# Sheet1.net
KiCad netlist of a schematic drawn in Altium Designer
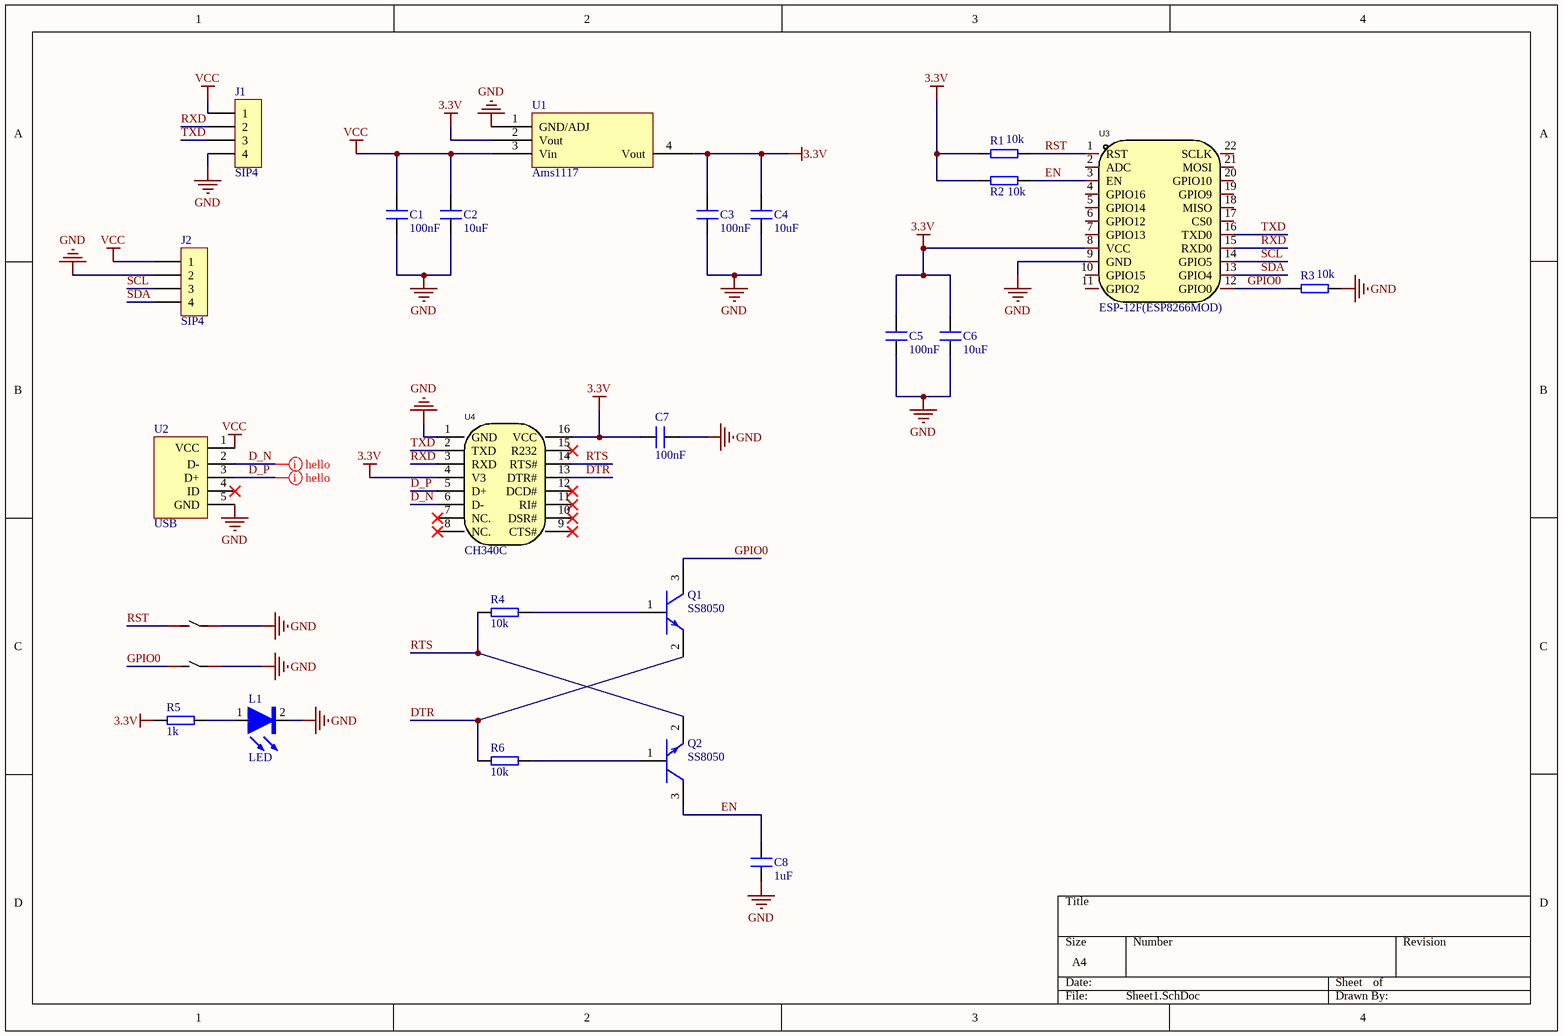
[diagram p0: Sheet1.SchDoc]

(export (version "E")
  (design (tool "Eeschema 10.0.6"))
  (components
    (comp (ref "C1")
      (value "100nF")
      (footprint "0805C")
      (description "电容")
      (libsource (lib "YTschlib") (part "CAP"))
    )
    (comp (ref "C2")
      (value "10uF")
      (footprint "0805C")
      (description "电容")
      (libsource (lib "YTschlib") (part "CAP"))
    )
    (comp (ref "C3")
      (value "100nF")
      (footprint "0805C")
      (description "电容")
      (libsource (lib "YTschlib") (part "CAP"))
    )
    (comp (ref "C4")
      (value "10uF")
      (footprint "0805C")
      (description "电容")
      (libsource (lib "YTschlib") (part "CAP"))
    )
    (comp (ref "C5")
      (value "100nF")
      (footprint "0805C")
      (description "电容")
      (libsource (lib "YTschlib") (part "CAP"))
    )
    (comp (ref "C6")
      (value "10uF")
      (footprint "0805C")
      (description "电容")
      (libsource (lib "YTschlib") (part "CAP"))
    )
    (comp (ref "C7")
      (value "100nF")
      (footprint "0805C")
      (description "电容")
      (libsource (lib "YTschlib") (part "CAP"))
    )
    (comp (ref "C8")
      (value "1uF")
      (footprint "0805C")
      (description "电容")
      (libsource (lib "YTschlib") (part "CAP"))
    )
    (comp (ref "J1")
      (value "SIP4")
      (footprint "XH2.54-WS-4P")
      (description "jointbar")
      (libsource (lib "YTschlib") (part "SIP4"))
    )
    (comp (ref "J2")
      (value "SIP4")
      (footprint "SIP_4P-P2.54-V-F")
      (description "jointbar")
      (libsource (lib "YTschlib") (part "SIP4"))
    )
    (comp (ref "L1") (value "LED") (footprint "LED0603-R-RD_GREEN") (libsource (lib "YTschlib") (part "LED")))
    (comp (ref "Q1")
      (value "SS8050")
      (footprint "SOT-23-3_L2.9-W1.3-P1.90-LS2.4-BR")
      (libsource (lib "YTschlib") (part "SS8050"))
    )
    (comp (ref "Q2")
      (value "SS8050")
      (footprint "SOT-23-3_L2.9-W1.3-P1.90-LS2.4-BR")
      (libsource (lib "YTschlib") (part "SS8050"))
    )
    (comp (ref "R1")
      (value "10k")
      (footprint "0805R")
      (description "电阻")
      (libsource (lib "YTschlib") (part "RES"))
    )
    (comp (ref "R2")
      (value "10k")
      (footprint "0805R")
      (description "电阻")
      (libsource (lib "YTschlib") (part "RES"))
    )
    (comp (ref "R3")
      (value "10k")
      (footprint "0805R")
      (description "电阻")
      (libsource (lib "YTschlib") (part "RES"))
    )
    (comp (ref "R4")
      (value "10k")
      (footprint "0805R")
      (description "电阻")
      (libsource (lib "YTschlib") (part "RES"))
    )
    (comp (ref "R5")
      (value "1k")
      (footprint "0805R")
      (description "电阻")
      (libsource (lib "YTschlib") (part "RES"))
    )
    (comp (ref "R6")
      (value "10k")
      (footprint "0805R")
      (description "电阻")
      (libsource (lib "YTschlib") (part "RES"))
    )
    (comp (ref "SW1")
      (value "TS342A2P 250gf-WZ 021_C2987973")
      (footprint "SW-SMD_L4.0-W2.9-LS5.0")
      (fields
        (field (name "MANUFACTURER") "SHOU HAN(首韩)")
        (field (name "MANUFACTURER PART") "TS342A2P 250gf-WZ 021")
      )
      (libsource (lib "YTschlib") (part "SW"))
    )
    (comp (ref "SW2")
      (value "TS342A2P 250gf-WZ 021_C2987973")
      (footprint "SW-SMD_L4.0-W2.9-LS5.0")
      (fields
        (field (name "MANUFACTURER") "SHOU HAN(首韩)")
        (field (name "MANUFACTURER PART") "TS342A2P 250gf-WZ 021")
      )
      (libsource (lib "YTschlib") (part "SW"))
    )
    (comp (ref "U1")
      (value "Ams1117")
      (footprint "SOT-223-4_L6.5-W3.5-P2.30-LS7.0-BR")
      (libsource (lib "YTschlib") (part "Ams1117"))
    )
    (comp (ref "U2") (value "USB") (footprint "USB-SMD_MINI-5PTP") (libsource (lib "YTschlib") (part "USB")))
    (comp (ref "U3")
      (value "ESP-12F(ESP8266MOD)")
      (footprint "ESP-12F_SMD")
      (fields (field (name "MANUFACTURER") "Ai-Thinker(安信可)"))
      (libsource (lib "YTschlib") (part "ESP-12F(ESP8266MOD)"))
    )
    (comp (ref "U4")
      (value "CH340C")
      (footprint "SOP16_L10.0-W3.9-P1.27-LS6.0-BL")
      (fields (field (name "MANUFACTURER") "WCH(南京沁恒)"))
      (libsource (lib "YTschlib") (part "CH340C"))
    )
  )
  (nets
    (net (code "1") (name "/DTR") (class "Default")
      (node (ref "Q1") (pin "2") (pinfunction "E_2") (pintype "passive"))
      (node (ref "R6") (pin "1") (pinfunction "1_1") (pintype "passive"))
      (node (ref "U4") (pin "13") (pinfunction "DTR#_13") (pintype "passive"))
    )
    (net (code "2") (name "/D_N") (class "Default")
      (node (ref "U2") (pin "2") (pinfunction "D-_2") (pintype "passive"))
      (node (ref "U4") (pin "6") (pinfunction "D-_6") (pintype "passive"))
    )
    (net (code "3") (name "/D_P") (class "Default")
      (node (ref "U2") (pin "3") (pinfunction "D+_3") (pintype "passive"))
      (node (ref "U4") (pin "5") (pinfunction "D+_5") (pintype "passive"))
    )
    (net (code "4") (name "/EN") (class "Default")
      (node (ref "C8") (pin "2") (pinfunction "2_2") (pintype "passive"))
      (node (ref "Q2") (pin "3") (pinfunction "C_3") (pintype "passive"))
      (node (ref "R2") (pin "2") (pinfunction "2_2") (pintype "passive"))
      (node (ref "U3") (pin "3") (pinfunction "EN_3") (pintype "passive"))
    )
    (net (code "5") (name "/GPIO0") (class "Default")
      (node (ref "Q1") (pin "3") (pinfunction "C_3") (pintype "passive"))
      (node (ref "R3") (pin "1") (pinfunction "1_1") (pintype "passive"))
      (node (ref "SW2") (pin "1") (pinfunction "1_1") (pintype "passive"))
      (node (ref "U3") (pin "12") (pinfunction "GPIO0_12") (pintype "passive"))
    )
    (net (code "6") (name "/RST") (class "Default")
      (node (ref "R1") (pin "2") (pinfunction "2_2") (pintype "passive"))
      (node (ref "SW1") (pin "1") (pinfunction "1_1") (pintype "passive"))
      (node (ref "U3") (pin "1") (pinfunction "RST_1") (pintype "passive"))
    )
    (net (code "7") (name "/RTS") (class "Default")
      (node (ref "Q2") (pin "2") (pinfunction "E_2") (pintype "passive"))
      (node (ref "R4") (pin "1") (pinfunction "1_1") (pintype "passive"))
      (node (ref "U4") (pin "14") (pinfunction "RTS#_14") (pintype "passive"))
    )
    (net (code "8") (name "/RXD") (class "Default")
      (node (ref "J1") (pin "2") (pinfunction "2_2") (pintype "passive"))
      (node (ref "U3") (pin "15") (pinfunction "RXD0_15") (pintype "passive"))
      (node (ref "U4") (pin "3") (pinfunction "RXD_3") (pintype "passive"))
    )
    (net (code "9") (name "/SCL") (class "Default")
      (node (ref "J2") (pin "3") (pinfunction "3_3") (pintype "passive"))
      (node (ref "U3") (pin "14") (pinfunction "GPIO5_14") (pintype "passive"))
    )
    (net (code "10") (name "/SDA") (class "Default")
      (node (ref "J2") (pin "4") (pinfunction "4_4") (pintype "passive"))
      (node (ref "U3") (pin "13") (pinfunction "GPIO4_13") (pintype "passive"))
    )
    (net (code "11") (name "/TXD") (class "Default")
      (node (ref "J1") (pin "3") (pinfunction "3_3") (pintype "passive"))
      (node (ref "U3") (pin "16") (pinfunction "TXD0_16") (pintype "passive"))
      (node (ref "U4") (pin "2") (pinfunction "TXD_2") (pintype "passive"))
    )
    (net (code "12") (name "3.3V") (class "Default")
      (node (ref "C3") (pin "2") (pinfunction "2_2") (pintype "passive"))
      (node (ref "C4") (pin "2") (pinfunction "2_2") (pintype "passive"))
      (node (ref "C5") (pin "2") (pinfunction "2_2") (pintype "passive"))
      (node (ref "C6") (pin "2") (pinfunction "2_2") (pintype "passive"))
      (node (ref "C7") (pin "1") (pinfunction "1_1") (pintype "passive"))
      (node (ref "R1") (pin "1") (pinfunction "1_1") (pintype "passive"))
      (node (ref "R2") (pin "1") (pinfunction "1_1") (pintype "passive"))
      (node (ref "R5") (pin "1") (pinfunction "1_1") (pintype "passive"))
      (node (ref "U1") (pin "2") (pinfunction "Vout_2") (pintype "power_in"))
      (node (ref "U1") (pin "4") (pinfunction "Vout_4") (pintype "power_in"))
      (node (ref "U3") (pin "8") (pinfunction "VCC_8") (pintype "passive"))
      (node (ref "U4") (pin "16") (pinfunction "VCC_16") (pintype "passive"))
      (node (ref "U4") (pin "4") (pinfunction "V3_4") (pintype "passive"))
    )
    (net (code "13") (name "GND") (class "Default")
      (node (ref "C1") (pin "1") (pinfunction "1_1") (pintype "passive"))
      (node (ref "C2") (pin "1") (pinfunction "1_1") (pintype "passive"))
      (node (ref "C3") (pin "1") (pinfunction "1_1") (pintype "passive"))
      (node (ref "C4") (pin "1") (pinfunction "1_1") (pintype "passive"))
      (node (ref "C5") (pin "1") (pinfunction "1_1") (pintype "passive"))
      (node (ref "C6") (pin "1") (pinfunction "1_1") (pintype "passive"))
      (node (ref "C7") (pin "2") (pinfunction "2_2") (pintype "passive"))
      (node (ref "C8") (pin "1") (pinfunction "1_1") (pintype "passive"))
      (node (ref "J1") (pin "4") (pinfunction "4_4") (pintype "passive"))
      (node (ref "J2") (pin "2") (pinfunction "2_2") (pintype "passive"))
      (node (ref "L1") (pin "2") (pinfunction "2_2") (pintype "passive"))
      (node (ref "R3") (pin "2") (pinfunction "2_2") (pintype "passive"))
      (node (ref "SW1") (pin "2") (pinfunction "2_2") (pintype "passive"))
      (node (ref "SW2") (pin "2") (pinfunction "2_2") (pintype "passive"))
      (node (ref "U1") (pin "1") (pinfunction "GND/ADJ_1") (pintype "power_in"))
      (node (ref "U2") (pin "5") (pinfunction "GND_5") (pintype "passive"))
      (node (ref "U3") (pin "9") (pinfunction "GND_9") (pintype "passive"))
      (node (ref "U4") (pin "1") (pinfunction "GND_1") (pintype "passive"))
    )
    (net (code "14") (name "Net-(L1-Pad1)") (class "Default")
      (node (ref "L1") (pin "1") (pinfunction "1_1") (pintype "passive"))
      (node (ref "R5") (pin "2") (pinfunction "2_2") (pintype "passive"))
    )
    (net (code "15") (name "Net-(Q1-B)") (class "Default")
      (node (ref "Q1") (pin "1") (pinfunction "B_1") (pintype "passive"))
      (node (ref "R4") (pin "2") (pinfunction "2_2") (pintype "passive"))
    )
    (net (code "16") (name "Net-(Q2-B)") (class "Default")
      (node (ref "Q2") (pin "1") (pinfunction "B_1") (pintype "passive"))
      (node (ref "R6") (pin "2") (pinfunction "2_2") (pintype "passive"))
    )
    (net (code "17") (name "VCC") (class "Default")
      (node (ref "C1") (pin "2") (pinfunction "2_2") (pintype "passive"))
      (node (ref "C2") (pin "2") (pinfunction "2_2") (pintype "passive"))
      (node (ref "J1") (pin "1") (pinfunction "1_1") (pintype "passive"))
      (node (ref "J2") (pin "1") (pinfunction "1_1") (pintype "passive"))
      (node (ref "U1") (pin "3") (pinfunction "Vin_3") (pintype "power_in"))
      (node (ref "U2") (pin "1") (pinfunction "VCC_1") (pintype "passive"))
    )
    (net (code "18") (name "unconnected-(U2-ID-Pad4)") (class "Default")
      (node (ref "U2") (pin "4") (pinfunction "ID_4") (pintype "passive+no_connect"))
    )
    (net (code "19") (name "unconnected-(U3-ADC-Pad2)") (class "Default")
      (node (ref "U3") (pin "2") (pinfunction "ADC_2") (pintype "passive"))
    )
    (net (code "20") (name "unconnected-(U3-CS0-Pad17)") (class "Default")
      (node (ref "U3") (pin "17") (pinfunction "CS0_17") (pintype "passive"))
    )
    (net (code "21") (name "unconnected-(U3-GPIO2-Pad11)") (class "Default")
      (node (ref "U3") (pin "11") (pinfunction "GPIO2_11") (pintype "passive"))
    )
    (net (code "22") (name "unconnected-(U3-GPIO9-Pad19)") (class "Default")
      (node (ref "U3") (pin "19") (pinfunction "GPIO9_19") (pintype "passive"))
    )
    (net (code "23") (name "unconnected-(U3-GPIO10-Pad20)") (class "Default")
      (node (ref "U3") (pin "20") (pinfunction "GPIO10_20") (pintype "passive"))
    )
    (net (code "24") (name "unconnected-(U3-GPIO12-Pad6)") (class "Default")
      (node (ref "U3") (pin "6") (pinfunction "GPIO12_6") (pintype "passive"))
    )
    (net (code "25") (name "unconnected-(U3-GPIO13-Pad7)") (class "Default")
      (node (ref "U3") (pin "7") (pinfunction "GPIO13_7") (pintype "passive"))
    )
    (net (code "26") (name "unconnected-(U3-GPIO14-Pad5)") (class "Default")
      (node (ref "U3") (pin "5") (pinfunction "GPIO14_5") (pintype "passive"))
    )
    (net (code "27") (name "unconnected-(U3-GPIO15-Pad10)") (class "Default")
      (node (ref "U3") (pin "10") (pinfunction "GPIO15_10") (pintype "passive"))
    )
    (net (code "28") (name "unconnected-(U3-GPIO16-Pad4)") (class "Default")
      (node (ref "U3") (pin "4") (pinfunction "GPIO16_4") (pintype "passive"))
    )
    (net (code "29") (name "unconnected-(U3-MISO-Pad18)") (class "Default")
      (node (ref "U3") (pin "18") (pinfunction "MISO_18") (pintype "passive"))
    )
    (net (code "30") (name "unconnected-(U3-MOSI-Pad21)") (class "Default")
      (node (ref "U3") (pin "21") (pinfunction "MOSI_21") (pintype "passive"))
    )
    (net (code "31") (name "unconnected-(U3-SCLK-Pad22)") (class "Default")
      (node (ref "U3") (pin "22") (pinfunction "SCLK_22") (pintype "passive"))
    )
    (net (code "32") (name "unconnected-(U4-CTS#-Pad9)") (class "Default")
      (node (ref "U4") (pin "9") (pinfunction "CTS#_9") (pintype "passive+no_connect"))
    )
    (net (code "33") (name "unconnected-(U4-DCD#-Pad12)") (class "Default")
      (node (ref "U4") (pin "12") (pinfunction "DCD#_12") (pintype "passive+no_connect"))
    )
    (net (code "34") (name "unconnected-(U4-DSR#-Pad10)") (class "Default")
      (node (ref "U4") (pin "10") (pinfunction "DSR#_10") (pintype "passive+no_connect"))
    )
    (net (code "35") (name "unconnected-(U4-NC.-Pad7)") (class "Default")
      (node (ref "U4") (pin "7") (pinfunction "NC._7") (pintype "passive+no_connect"))
    )
    (net (code "36") (name "unconnected-(U4-NC.-Pad8)") (class "Default")
      (node (ref "U4") (pin "8") (pinfunction "NC._8") (pintype "passive+no_connect"))
    )
    (net (code "37") (name "unconnected-(U4-R232-Pad15)") (class "Default")
      (node (ref "U4") (pin "15") (pinfunction "R232_15") (pintype "passive+no_connect"))
    )
    (net (code "38") (name "unconnected-(U4-RI#-Pad11)") (class "Default")
      (node (ref "U4") (pin "11") (pinfunction "RI#_11") (pintype "passive+no_connect"))
    )
  )
)
